# Braumister_V_2_0.net
KiCad netlist of a schematic drawn in EAGLE
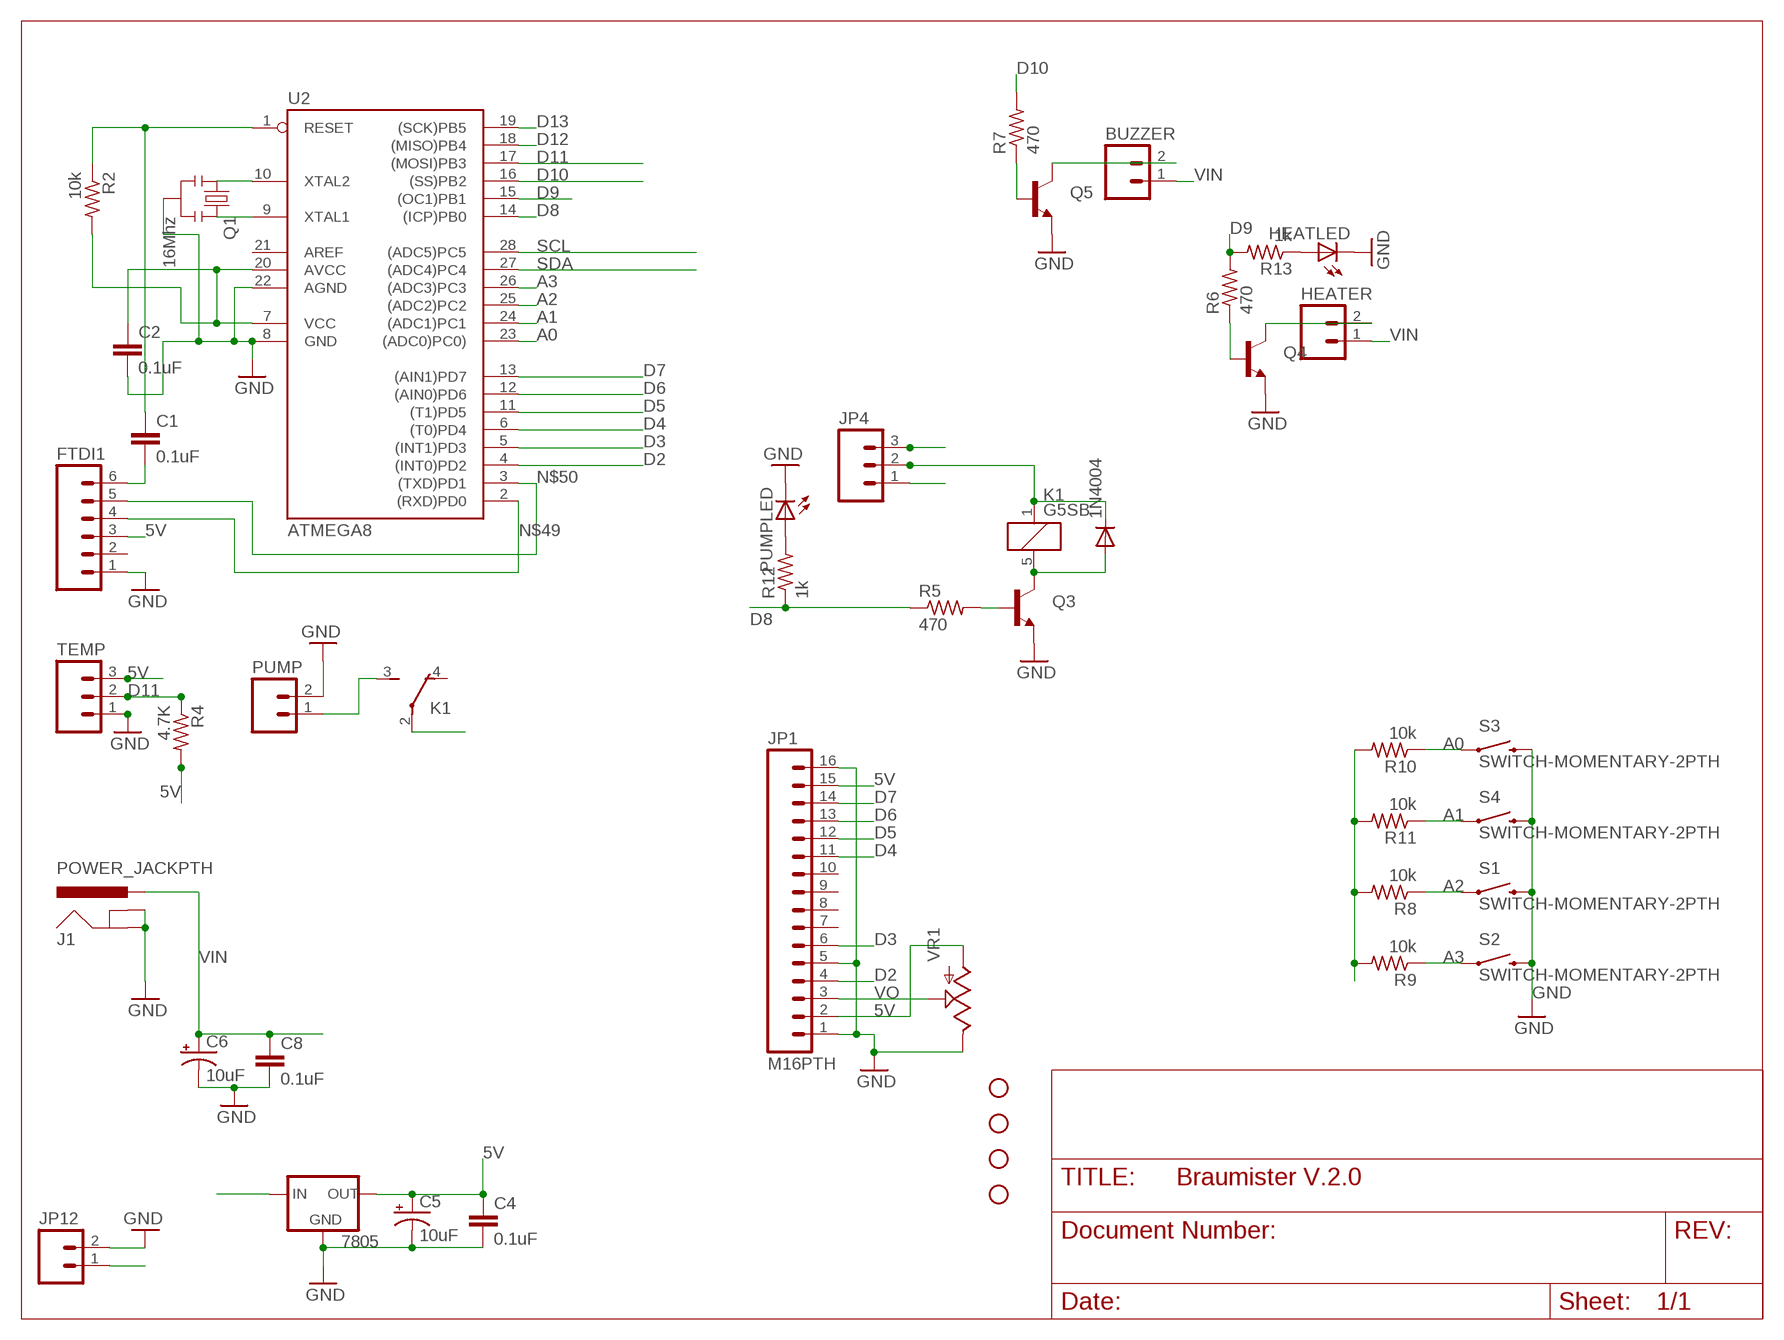
[diagram p0: schematic, sheet 1]

(export (version "E")
  (design (tool "Eeschema 10.0.6"))
  (components
    (comp (ref "1N4004")
      (value "DIODEPTH")
      (footprint "eagle-import:DIODE-1N4001")
      (libsource (lib "eagle-import") (part "DIODEPTH"))
    )
    (comp (ref "7805")
      (value "V_REG_78XX")
      (footprint "eagle-import:TO220AHV")
      (libsource (lib "eagle-import") (part "V_REG_78XX"))
    )
    (comp (ref "BUZZER")
      (value "M023.5MM")
      (footprint "eagle-import:SCREWTERMINAL-3.5MM-2")
      (libsource (lib "eagle-import") (part "M023.5MM"))
    )
    (comp (ref "C1")
      (value "0.1uF")
      (footprint "eagle-import:CAP-PTH-SMALL")
      (libsource (lib "eagle-import") (part "CAPPTH"))
    )
    (comp (ref "C2")
      (value "0.1uF")
      (footprint "eagle-import:CAP-PTH-SMALL")
      (libsource (lib "eagle-import") (part "CAPPTH"))
    )
    (comp (ref "C4")
      (value "0.1uF")
      (footprint "eagle-import:CAP-PTH-SMALL")
      (libsource (lib "eagle-import") (part "CAPPTH"))
    )
    (comp (ref "C5")
      (value "10uF")
      (footprint "eagle-import:CAP6.3MM2.5MM")
      (libsource (lib "eagle-import") (part "CAP_POL6.3MMPTH"))
    )
    (comp (ref "C6")
      (value "10uF")
      (footprint "eagle-import:CAP6.3MM2.5MM")
      (libsource (lib "eagle-import") (part "CAP_POL6.3MMPTH"))
    )
    (comp (ref "C8")
      (value "0.1uF")
      (footprint "eagle-import:CAP-PTH-SMALL")
      (libsource (lib "eagle-import") (part "CAPPTH"))
    )
    (comp (ref "FTDI1")
      (value "M06SIP")
      (footprint "eagle-import:1X06")
      (libsource (lib "eagle-import") (part "M06SIP"))
    )
    (comp (ref "HEATER")
      (value "M023.5MM")
      (footprint "eagle-import:SCREWTERMINAL-3.5MM-2")
      (libsource (lib "eagle-import") (part "M023.5MM"))
    )
    (comp (ref "HEATLED")
      (value "LED3MM")
      (footprint "eagle-import:LED3MM")
      (libsource (lib "eagle-import") (part "LED3MM"))
    )
    (comp (ref "J1")
      (value "POWER_JACKPTH")
      (footprint "eagle-import:POWER_JACK_PTH")
      (libsource (lib "eagle-import") (part "POWER_JACKPTH"))
    )
    (comp (ref "JP1")
      (value "M16PTH")
      (footprint "eagle-import:1X16")
      (libsource (lib "eagle-import") (part "M16PTH"))
    )
    (comp (ref "JP2")
      (value "STAND-OFF")
      (footprint "eagle-import:STAND-OFF")
      (libsource (lib "eagle-import") (part "STAND-OFF"))
    )
    (comp (ref "JP4")
      (value "M03LOCK")
      (footprint "eagle-import:1X03_LOCK")
      (libsource (lib "eagle-import") (part "M03LOCK"))
    )
    (comp (ref "JP7")
      (value "STAND-OFF")
      (footprint "eagle-import:STAND-OFF")
      (libsource (lib "eagle-import") (part "STAND-OFF"))
    )
    (comp (ref "JP9")
      (value "STAND-OFF")
      (footprint "eagle-import:STAND-OFF")
      (libsource (lib "eagle-import") (part "STAND-OFF"))
    )
    (comp (ref "JP10")
      (value "STAND-OFF")
      (footprint "eagle-import:STAND-OFF")
      (libsource (lib "eagle-import") (part "STAND-OFF"))
    )
    (comp (ref "JP12")
      (value "M02PTH")
      (footprint "eagle-import:1X02")
      (libsource (lib "eagle-import") (part "_allyourbase_M02PTH"))
    )
    (comp (ref "K1")
      (value "G5SB")
      (footprint "eagle-import:G5SB")
      (libsource (lib "eagle-import") (part "G5SB"))
    )
    (comp (ref "PUMP")
      (value "M023.5MM")
      (footprint "eagle-import:SCREWTERMINAL-3.5MM-2")
      (libsource (lib "eagle-import") (part "M023.5MM"))
    )
    (comp (ref "PUMPLED")
      (value "LED3MM")
      (footprint "eagle-import:LED3MM")
      (libsource (lib "eagle-import") (part "LED3MM"))
    )
    (comp (ref "Q1")
      (value "16Mhz")
      (footprint "eagle-import:RESONATOR-PTH")
      (libsource (lib "eagle-import") (part "RESONATORPTH"))
    )
    (comp (ref "Q3")
      (value "TRANSISTOR_NPNTO-92-AMMO")
      (footprint "eagle-import:TO-92-AMMO")
      (libsource (lib "eagle-import") (part "TRANSISTOR_NPNTO-92-AMMO"))
    )
    (comp (ref "Q4")
      (value "TRANSISTOR_NPNTO-92-AMMO")
      (footprint "eagle-import:TO-92-AMMO")
      (libsource (lib "eagle-import") (part "TRANSISTOR_NPNTO-92-AMMO"))
    )
    (comp (ref "Q5")
      (value "TRANSISTOR_NPNTO-92-AMMO")
      (footprint "eagle-import:TO-92-AMMO")
      (libsource (lib "eagle-import") (part "TRANSISTOR_NPNTO-92-AMMO"))
    )
    (comp (ref "R2")
      (value "10k")
      (footprint "eagle-import:0204_7")
      (libsource (lib "eagle-import") (part "R-US_0204/7"))
    )
    (comp (ref "R4")
      (value "4.7K")
      (footprint "eagle-import:0204_7")
      (libsource (lib "eagle-import") (part "R-US_0204/7"))
    )
    (comp (ref "R5")
      (value "470")
      (footprint "eagle-import:0204_7")
      (libsource (lib "eagle-import") (part "R-US_0204/7"))
    )
    (comp (ref "R6")
      (value "470")
      (footprint "eagle-import:0204_7")
      (libsource (lib "eagle-import") (part "R-US_0204/7"))
    )
    (comp (ref "R7")
      (value "470")
      (footprint "eagle-import:0204_7")
      (libsource (lib "eagle-import") (part "R-US_0204/7"))
    )
    (comp (ref "R8")
      (value "10k")
      (footprint "eagle-import:0204_7")
      (libsource (lib "eagle-import") (part "R-US_0204/7"))
    )
    (comp (ref "R9")
      (value "10k")
      (footprint "eagle-import:0204_7")
      (libsource (lib "eagle-import") (part "R-US_0204/7"))
    )
    (comp (ref "R10")
      (value "10k")
      (footprint "eagle-import:0204_7")
      (libsource (lib "eagle-import") (part "R-US_0204/7"))
    )
    (comp (ref "R11")
      (value "10k")
      (footprint "eagle-import:0204_7")
      (libsource (lib "eagle-import") (part "R-US_0204/7"))
    )
    (comp (ref "R12")
      (value "1k")
      (footprint "eagle-import:0204_7")
      (libsource (lib "eagle-import") (part "R-US_0204/7"))
    )
    (comp (ref "R13")
      (value "1k")
      (footprint "eagle-import:0204_7")
      (libsource (lib "eagle-import") (part "R-US_0204/7"))
    )
    (comp (ref "S1")
      (value "SWITCH-MOMENTARY-2PTH")
      (footprint "eagle-import:TACTILE-PTH")
      (libsource (lib "eagle-import") (part "SWITCH-MOMENTARY-2PTH"))
    )
    (comp (ref "S2")
      (value "SWITCH-MOMENTARY-2PTH")
      (footprint "eagle-import:TACTILE-PTH")
      (libsource (lib "eagle-import") (part "SWITCH-MOMENTARY-2PTH"))
    )
    (comp (ref "S3")
      (value "SWITCH-MOMENTARY-2PTH")
      (footprint "eagle-import:TACTILE-PTH")
      (libsource (lib "eagle-import") (part "SWITCH-MOMENTARY-2PTH"))
    )
    (comp (ref "S4")
      (value "SWITCH-MOMENTARY-2PTH")
      (footprint "eagle-import:TACTILE-PTH")
      (libsource (lib "eagle-import") (part "SWITCH-MOMENTARY-2PTH"))
    )
    (comp (ref "TEMP")
      (value "M03SCREW")
      (footprint "eagle-import:SCREWTERMINAL-3.5MM-3")
      (libsource (lib "eagle-import") (part "M03SCREW"))
    )
    (comp (ref "U2")
      (value "ATMEGA8")
      (footprint "eagle-import:DIL28-3")
      (libsource (lib "eagle-import") (part "AT90S4433P"))
    )
    (comp (ref "VR1")
      (value "POT")
      (footprint "eagle-import:TRIM_POT_SIDE")
      (libsource (lib "eagle-import") (part "POT"))
    )
  )
  (nets
    (net (code "1") (name "/5V") (class "Default")
      (node (ref "7805") (pin "E") (pinfunction "OUT_E") (pintype "output"))
      (node (ref "C2") (pin "1") (pinfunction "1_1") (pintype "passive"))
      (node (ref "C4") (pin "1") (pinfunction "1_1") (pintype "passive"))
      (node (ref "C5") (pin "P$2") (pinfunction "+_P$2") (pintype "passive"))
      (node (ref "FTDI1") (pin "3") (pinfunction "3_3") (pintype "passive"))
      (node (ref "JP1") (pin "15") (pinfunction "15_15") (pintype "passive"))
      (node (ref "JP1") (pin "2") (pinfunction "2_2") (pintype "passive"))
      (node (ref "JP4") (pin "3") (pinfunction "3_3") (pintype "passive"))
      (node (ref "R10") (pin "2") (pinfunction "2_2") (pintype "passive"))
      (node (ref "R11") (pin "2") (pinfunction "2_2") (pintype "passive"))
      (node (ref "R2") (pin "2") (pinfunction "2_2") (pintype "passive"))
      (node (ref "R4") (pin "2") (pinfunction "2_2") (pintype "passive"))
      (node (ref "R8") (pin "2") (pinfunction "2_2") (pintype "passive"))
      (node (ref "R9") (pin "2") (pinfunction "2_2") (pintype "passive"))
      (node (ref "TEMP") (pin "3") (pinfunction "3_3") (pintype "passive"))
      (node (ref "U2") (pin "20") (pinfunction "AVCC_20") (pintype "power_in"))
      (node (ref "U2") (pin "7") (pinfunction "VCC_7") (pintype "power_in"))
      (node (ref "VR1") (pin "P$3") (pinfunction "A_P$3") (pintype "passive"))
    )
    (net (code "2") (name "/A0") (class "Default")
      (node (ref "R10") (pin "1") (pinfunction "1_1") (pintype "passive"))
      (node (ref "S3") (pin "1") (pinfunction "1_1") (pintype "passive"))
      (node (ref "U2") (pin "23") (pinfunction "(ADC0)PC0)_23") (pintype "bidirectional"))
    )
    (net (code "3") (name "/A1") (class "Default")
      (node (ref "R11") (pin "1") (pinfunction "1_1") (pintype "passive"))
      (node (ref "S4") (pin "1") (pinfunction "1_1") (pintype "passive"))
      (node (ref "U2") (pin "24") (pinfunction "(ADC1)PC1_24") (pintype "bidirectional"))
    )
    (net (code "4") (name "/A2") (class "Default")
      (node (ref "R8") (pin "1") (pinfunction "1_1") (pintype "passive"))
      (node (ref "S1") (pin "1") (pinfunction "1_1") (pintype "passive"))
      (node (ref "U2") (pin "25") (pinfunction "(ADC2)PC2_25") (pintype "bidirectional"))
    )
    (net (code "5") (name "/A3") (class "Default")
      (node (ref "R9") (pin "1") (pinfunction "1_1") (pintype "passive"))
      (node (ref "S2") (pin "1") (pinfunction "1_1") (pintype "passive"))
      (node (ref "U2") (pin "26") (pinfunction "(ADC3)PC3_26") (pintype "bidirectional"))
    )
    (net (code "6") (name "/D2") (class "Default")
      (node (ref "JP1") (pin "4") (pinfunction "4_4") (pintype "passive"))
      (node (ref "U2") (pin "4") (pinfunction "(INT0)PD2_4") (pintype "bidirectional"))
    )
    (net (code "7") (name "/D3") (class "Default")
      (node (ref "JP1") (pin "6") (pinfunction "6_6") (pintype "passive"))
      (node (ref "U2") (pin "5") (pinfunction "(INT1)PD3_5") (pintype "bidirectional"))
    )
    (net (code "8") (name "/D4") (class "Default")
      (node (ref "JP1") (pin "11") (pinfunction "11_11") (pintype "passive"))
      (node (ref "U2") (pin "6") (pinfunction "(T0)PD4_6") (pintype "bidirectional"))
    )
    (net (code "9") (name "/D5") (class "Default")
      (node (ref "JP1") (pin "12") (pinfunction "12_12") (pintype "passive"))
      (node (ref "U2") (pin "11") (pinfunction "(T1)PD5_11") (pintype "bidirectional"))
    )
    (net (code "10") (name "/D6") (class "Default")
      (node (ref "JP1") (pin "13") (pinfunction "13_13") (pintype "passive"))
      (node (ref "U2") (pin "12") (pinfunction "(AIN0)PD6_12") (pintype "bidirectional"))
    )
    (net (code "11") (name "/D7") (class "Default")
      (node (ref "JP1") (pin "14") (pinfunction "14_14") (pintype "passive"))
      (node (ref "U2") (pin "13") (pinfunction "(AIN1)PD7_13") (pintype "bidirectional"))
    )
    (net (code "12") (name "/D8") (class "Default")
      (node (ref "R12") (pin "1") (pinfunction "1_1") (pintype "passive"))
      (node (ref "R5") (pin "1") (pinfunction "1_1") (pintype "passive"))
      (node (ref "U2") (pin "14") (pinfunction "(ICP)PB0_14") (pintype "bidirectional"))
    )
    (net (code "13") (name "/D9") (class "Default")
      (node (ref "R13") (pin "2") (pinfunction "2_2") (pintype "passive"))
      (node (ref "R6") (pin "2") (pinfunction "2_2") (pintype "passive"))
      (node (ref "U2") (pin "15") (pinfunction "(OC1)PB1_15") (pintype "bidirectional"))
    )
    (net (code "14") (name "/D10") (class "Default")
      (node (ref "R7") (pin "2") (pinfunction "2_2") (pintype "passive"))
      (node (ref "U2") (pin "16") (pinfunction "(SS)PB2_16") (pintype "bidirectional"))
    )
    (net (code "15") (name "/D11") (class "Default")
      (node (ref "R4") (pin "1") (pinfunction "1_1") (pintype "passive"))
      (node (ref "TEMP") (pin "2") (pinfunction "2_2") (pintype "passive"))
      (node (ref "U2") (pin "17") (pinfunction "(MOSI)PB3_17") (pintype "bidirectional"))
    )
    (net (code "16") (name "/D12") (class "Default")
      (node (ref "U2") (pin "18") (pinfunction "(MISO)PB4_18") (pintype "bidirectional"))
    )
    (net (code "17") (name "/D13") (class "Default")
      (node (ref "U2") (pin "19") (pinfunction "(SCK)PB5_19") (pintype "bidirectional"))
    )
    (net (code "18") (name "/N$49") (class "Default")
      (node (ref "FTDI1") (pin "4") (pinfunction "4_4") (pintype "passive"))
      (node (ref "U2") (pin "2") (pinfunction "(RXD)PD0_2") (pintype "bidirectional"))
    )
    (net (code "19") (name "/N$50") (class "Default")
      (node (ref "FTDI1") (pin "5") (pinfunction "5_5") (pintype "passive"))
      (node (ref "U2") (pin "3") (pinfunction "(TXD)PD1_3") (pintype "bidirectional"))
    )
    (net (code "20") (name "/SCL") (class "Default")
      (node (ref "U2") (pin "28") (pinfunction "(ADC5)PC5_28") (pintype "bidirectional"))
    )
    (net (code "21") (name "/SDA") (class "Default")
      (node (ref "U2") (pin "27") (pinfunction "(ADC4)PC4_27") (pintype "bidirectional"))
    )
    (net (code "22") (name "/VIN") (class "Default")
      (node (ref "7805") (pin "B") (pinfunction "IN_B") (pintype "input"))
      (node (ref "BUZZER") (pin "1") (pinfunction "1_1") (pintype "passive"))
      (node (ref "C6") (pin "P$2") (pinfunction "+_P$2") (pintype "passive"))
      (node (ref "C8") (pin "1") (pinfunction "1_1") (pintype "passive"))
      (node (ref "HEATER") (pin "1") (pinfunction "1_1") (pintype "passive"))
      (node (ref "J1") (pin "PWR") (pinfunction "PWR_PWR") (pintype "bidirectional"))
      (node (ref "JP12") (pin "1") (pinfunction "1_1") (pintype "passive"))
      (node (ref "JP4") (pin "1") (pinfunction "1_1") (pintype "passive"))
      (node (ref "K1") (pin "2") (pinfunction "P_2") (pintype "passive"))
    )
    (net (code "23") (name "/VO") (class "Default")
      (node (ref "JP1") (pin "3") (pinfunction "3_3") (pintype "passive"))
      (node (ref "VR1") (pin "P$2") (pinfunction "S_P$2") (pintype "passive"))
    )
    (net (code "24") (name "GND") (class "Default")
      (node (ref "7805") (pin "C") (pinfunction "GND_C") (pintype "input"))
      (node (ref "C2") (pin "2") (pinfunction "2_2") (pintype "passive"))
      (node (ref "C4") (pin "2") (pinfunction "2_2") (pintype "passive"))
      (node (ref "C5") (pin "P$1") (pinfunction "-_P$1") (pintype "passive"))
      (node (ref "C6") (pin "P$1") (pinfunction "-_P$1") (pintype "passive"))
      (node (ref "C8") (pin "2") (pinfunction "2_2") (pintype "passive"))
      (node (ref "FTDI1") (pin "1") (pinfunction "1_1") (pintype "passive"))
      (node (ref "HEATLED") (pin "K") (pinfunction "C_K") (pintype "passive"))
      (node (ref "J1") (pin "GND") (pinfunction "GND_GND") (pintype "bidirectional"))
      (node (ref "J1") (pin "GNDBREAK") (pinfunction "GNDBREAK_GNDBREAK") (pintype "bidirectional"))
      (node (ref "JP1") (pin "1") (pinfunction "1_1") (pintype "passive"))
      (node (ref "JP1") (pin "16") (pinfunction "16_16") (pintype "passive"))
      (node (ref "JP1") (pin "5") (pinfunction "5_5") (pintype "passive"))
      (node (ref "JP12") (pin "2") (pinfunction "2_2") (pintype "passive"))
      (node (ref "PUMP") (pin "2") (pinfunction "2_2") (pintype "passive"))
      (node (ref "PUMPLED") (pin "K") (pinfunction "C_K") (pintype "passive"))
      (node (ref "Q1") (pin "2") (pinfunction "2_2") (pintype "passive"))
      (node (ref "Q3") (pin "1") (pinfunction "E_1") (pintype "passive"))
      (node (ref "Q4") (pin "1") (pinfunction "E_1") (pintype "passive"))
      (node (ref "Q5") (pin "1") (pinfunction "E_1") (pintype "passive"))
      (node (ref "S1") (pin "3") (pinfunction "2_3") (pintype "passive"))
      (node (ref "S2") (pin "3") (pinfunction "2_3") (pintype "passive"))
      (node (ref "S3") (pin "3") (pinfunction "2_3") (pintype "passive"))
      (node (ref "S4") (pin "3") (pinfunction "2_3") (pintype "passive"))
      (node (ref "TEMP") (pin "1") (pinfunction "1_1") (pintype "passive"))
      (node (ref "U2") (pin "22") (pinfunction "AGND_22") (pintype "power_in"))
      (node (ref "U2") (pin "8") (pinfunction "GND_8") (pintype "power_in"))
      (node (ref "VR1") (pin "P$1") (pinfunction "E_P$1") (pintype "passive"))
    )
    (net (code "25") (name "Net-(1N4004-PadC)") (class "Default")
      (node (ref "1N4004") (pin "C") (pinfunction "C_C") (pintype "passive"))
      (node (ref "JP4") (pin "2") (pinfunction "2_2") (pintype "passive"))
      (node (ref "K1") (pin "1") (pinfunction "1_1") (pintype "passive"))
    )
    (net (code "26") (name "Net-(C1-Pad2)") (class "Default")
      (node (ref "C1") (pin "2") (pinfunction "2_2") (pintype "passive"))
      (node (ref "FTDI1") (pin "6") (pinfunction "6_6") (pintype "passive"))
    )
    (net (code "27") (name "Net-(HEATLED-PadA)") (class "Default")
      (node (ref "HEATLED") (pin "A") (pinfunction "A_A") (pintype "passive"))
      (node (ref "R13") (pin "1") (pinfunction "1_1") (pintype "passive"))
    )
    (net (code "28") (name "Net-(K1A-2)") (class "Default")
      (node (ref "1N4004") (pin "A") (pinfunction "A_A") (pintype "passive"))
      (node (ref "K1") (pin "5") (pinfunction "2_5") (pintype "passive"))
      (node (ref "Q3") (pin "3") (pinfunction "C_3") (pintype "passive"))
    )
    (net (code "29") (name "Net-(K1B-S)") (class "Default")
      (node (ref "K1") (pin "3") (pinfunction "S_3") (pintype "passive"))
      (node (ref "PUMP") (pin "1") (pinfunction "1_1") (pintype "passive"))
    )
    (net (code "30") (name "Net-(PUMPLED-PadA)") (class "Default")
      (node (ref "PUMPLED") (pin "A") (pinfunction "A_A") (pintype "passive"))
      (node (ref "R12") (pin "2") (pinfunction "2_2") (pintype "passive"))
    )
    (net (code "31") (name "Net-(Q3-B)") (class "Default")
      (node (ref "Q3") (pin "2") (pinfunction "B_2") (pintype "passive"))
      (node (ref "R5") (pin "2") (pinfunction "2_2") (pintype "passive"))
    )
    (net (code "32") (name "Net-(Q4-B)") (class "Default")
      (node (ref "Q4") (pin "2") (pinfunction "B_2") (pintype "passive"))
      (node (ref "R6") (pin "1") (pinfunction "1_1") (pintype "passive"))
    )
    (net (code "33") (name "Net-(Q4-C)") (class "Default")
      (node (ref "HEATER") (pin "2") (pinfunction "2_2") (pintype "passive"))
      (node (ref "Q4") (pin "3") (pinfunction "C_3") (pintype "passive"))
    )
    (net (code "34") (name "Net-(Q5-B)") (class "Default")
      (node (ref "Q5") (pin "2") (pinfunction "B_2") (pintype "passive"))
      (node (ref "R7") (pin "1") (pinfunction "1_1") (pintype "passive"))
    )
    (net (code "35") (name "Net-(Q5-C)") (class "Default")
      (node (ref "BUZZER") (pin "2") (pinfunction "2_2") (pintype "passive"))
      (node (ref "Q5") (pin "3") (pinfunction "C_3") (pintype "passive"))
    )
    (net (code "36") (name "Net-(U2-RESET)") (class "Default")
      (node (ref "C1") (pin "1") (pinfunction "1_1") (pintype "passive"))
      (node (ref "R2") (pin "1") (pinfunction "1_1") (pintype "passive"))
      (node (ref "U2") (pin "1") (pinfunction "RESET_1") (pintype "input"))
    )
    (net (code "37") (name "Net-(U2-XTAL1)") (class "Default")
      (node (ref "Q1") (pin "3") (pinfunction "3_3") (pintype "passive"))
      (node (ref "U2") (pin "9") (pinfunction "XTAL1_9") (pintype "bidirectional"))
    )
    (net (code "38") (name "Net-(U2-XTAL2)") (class "Default")
      (node (ref "Q1") (pin "1") (pinfunction "1_1") (pintype "passive"))
      (node (ref "U2") (pin "10") (pinfunction "XTAL2_10") (pintype "bidirectional"))
    )
    (net (code "39") (name "unconnected-(FTDI1-Pad2)") (class "Default")
      (node (ref "FTDI1") (pin "2") (pinfunction "2_2") (pintype "passive"))
    )
    (net (code "40") (name "unconnected-(JP1-Pad7)") (class "Default")
      (node (ref "JP1") (pin "7") (pinfunction "7_7") (pintype "passive"))
    )
    (net (code "41") (name "unconnected-(JP1-Pad8)") (class "Default")
      (node (ref "JP1") (pin "8") (pinfunction "8_8") (pintype "passive"))
    )
    (net (code "42") (name "unconnected-(JP1-Pad9)") (class "Default")
      (node (ref "JP1") (pin "9") (pinfunction "9_9") (pintype "passive"))
    )
    (net (code "43") (name "unconnected-(JP1-Pad10)") (class "Default")
      (node (ref "JP1") (pin "10") (pinfunction "10_10") (pintype "passive"))
    )
    (net (code "44") (name "unconnected-(K1B-O-Pad4)") (class "Default")
      (node (ref "K1") (pin "4") (pinfunction "O_4") (pintype "passive"))
    )
    (net (code "45") (name "unconnected-(U2-AREF-Pad21)") (class "Default")
      (node (ref "U2") (pin "21") (pinfunction "AREF_21") (pintype "passive"))
    )
  )
)
